# RotaryDebouncer.net
KiCad netlist of a schematic drawn in Altium Designer
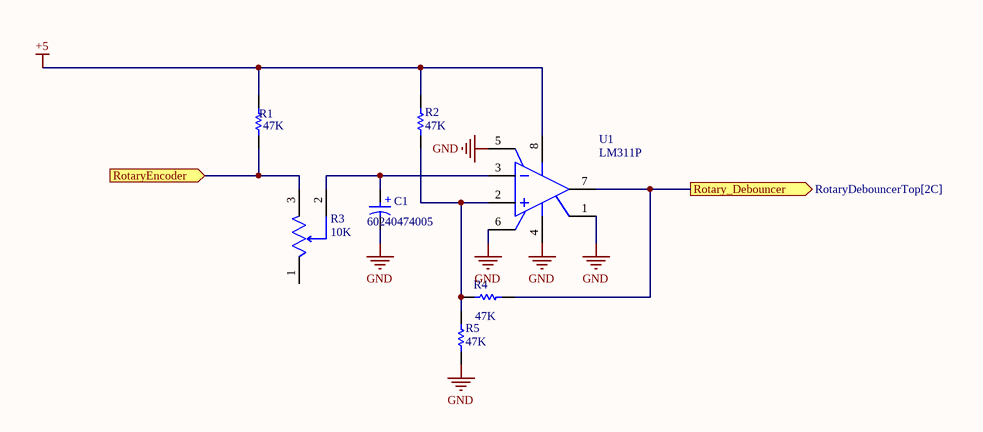
[diagram p0: RotaryDebouncer.SchDoc]

(export (version "E")
  (design (tool "Eeschema 10.0.6"))
  (components
    (comp (ref "C1")
      (value "60240474005")
      (footprint "WCAP-AT1H_D8H11.5")
      (description "860240474005 WCAP-AT1H Aluminum Electrolytic Capacitors")
      (fields (field (name "TOLERANCE") "20%"))
      (libsource (lib "Altium Content Vault") (part "Capacitor_Polarized"))
    )
    (comp (ref "R1")
      (value "47K")
      (footprint "RESA60-630X240")
      (description "Axial Resistor, 100 KOhm, +/- 1%, 0.25 W, -55 to 155 degC, 2-Pin THD, RoHS, Bulk")
      (fields (field (name "TOLERANCE") "1%"))
      (libsource (lib "Altium Content Vault") (part "RES-2"))
    )
    (comp (ref "R2")
      (value "47K")
      (footprint "RESA60-630X240")
      (description "Axial Resistor, 100 KOhm, +/- 1%, 0.25 W, -55 to 155 degC, 2-Pin THD, RoHS, Bulk")
      (fields (field (name "TOLERANCE") "1%"))
      (libsource (lib "Altium Content Vault") (part "RES-2"))
    )
    (comp (ref "R3")
      (value "10K")
      (footprint "FP-3296W-MFG")
      (description "TRIMMER 2K OHM 0.5W PC PIN TOP")
      (fields (field (name "TOLERANCE") "10%"))
      (libsource (lib "Altium Content Vault") (part "81a8d1f2e6c155a1fa928b358d1a42a"))
    )
    (comp (ref "R4")
      (value "47K")
      (footprint "RESA60-630X240")
      (description "Axial Resistor, 100 KOhm, +/- 1%, 0.25 W, -55 to 155 degC, 2-Pin THD, RoHS, Bulk")
      (fields (field (name "TOLERANCE") "1%"))
      (libsource (lib "Altium Content Vault") (part "RES-2"))
    )
    (comp (ref "R5")
      (value "47K")
      (footprint "RESA60-630X240")
      (description "Axial Resistor, 100 KOhm, +/- 1%, 0.25 W, -55 to 155 degC, 2-Pin THD, RoHS, Bulk")
      (fields (field (name "TOLERANCE") "1%"))
      (libsource (lib "Altium Content Vault") (part "RES-2"))
    )
    (comp (ref "U1")
      (value "LM311P")
      (footprint "FP-P0008A-MFG")
      (fields (field (name "TOLERANCE") "1%"))
      (libsource (lib "Altium Content Vault") (part "b2b1c66385073ed7f685b7e01cc60c1"))
    )
  )
  (nets
    (net (code "1") (name "+5") (class "Default")
      (node (ref "R1") (pin "2") (pinfunction "2_2") (pintype "passive"))
      (node (ref "R2") (pin "2") (pinfunction "2_2") (pintype "passive"))
      (node (ref "U1") (pin "8") (pinfunction "VCC+_8") (pintype "power_in"))
    )
    (net (code "2") (name "/RotaryEncoder") (class "Default")
      (node (ref "R1") (pin "1") (pinfunction "1_1") (pintype "passive"))
      (node (ref "R3") (pin "3") (pinfunction "CW_3") (pintype "passive"))
    )
    (net (code "3") (name "/Rotary_Debouncer") (class "Default")
      (node (ref "R4") (pin "2") (pinfunction "2_2") (pintype "passive"))
      (node (ref "U1") (pin "7") (pinfunction "COL_OUT_7") (pintype "open_collector"))
    )
    (net (code "4") (name "GND") (class "Default")
      (node (ref "C1") (pin "2") (pinfunction "N_2") (pintype "passive"))
      (node (ref "R5") (pin "1") (pinfunction "1_1") (pintype "passive"))
      (node (ref "U1") (pin "1") (pinfunction "EMIT_OUT_1") (pintype "open_emitter"))
      (node (ref "U1") (pin "4") (pinfunction "VCC-_4") (pintype "power_in"))
      (node (ref "U1") (pin "5") (pinfunction "BALANCE_5") (pintype "passive"))
      (node (ref "U1") (pin "6") (pinfunction "BAL/STRB_6") (pintype "passive"))
    )
    (net (code "5") (name "Net-(C1-P)") (class "Default")
      (node (ref "C1") (pin "1") (pinfunction "P_1") (pintype "passive"))
      (node (ref "R3") (pin "2") (pinfunction "WIPER_2") (pintype "passive"))
      (node (ref "U1") (pin "3") (pinfunction "IN-_3") (pintype "tri_state"))
    )
    (net (code "6") (name "Net-(U1-IN+)") (class "Default")
      (node (ref "R2") (pin "1") (pinfunction "1_1") (pintype "passive"))
      (node (ref "R4") (pin "1") (pinfunction "1_1") (pintype "passive"))
      (node (ref "R5") (pin "2") (pinfunction "2_2") (pintype "passive"))
      (node (ref "U1") (pin "2") (pinfunction "IN+_2") (pintype "tri_state"))
    )
    (net (code "7") (name "unconnected-(R3-CCW-Pad1)") (class "Default")
      (node (ref "R3") (pin "1") (pinfunction "CCW_1") (pintype "passive"))
    )
  )
)
